# tractor.net
KiCad netlist of a schematic drawn in EAGLE
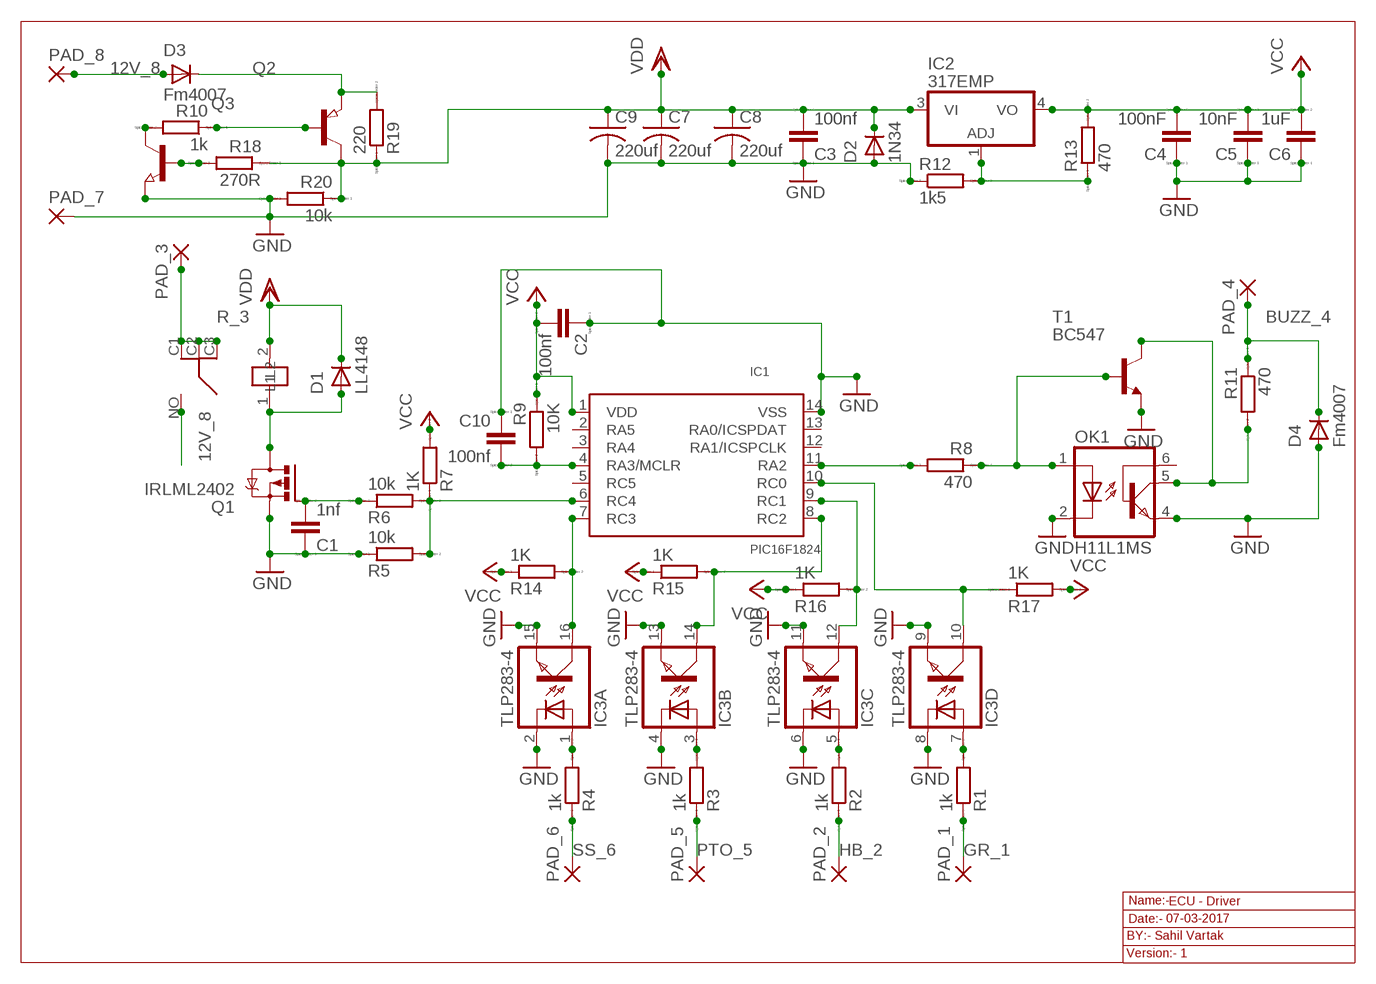
[diagram p0: schematic, sheet 1]

(export (version "E")
  (design (tool "Eeschema 10.0.6"))
  (components
    (comp (ref "C1")
      (value "1nf")
      (footprint "eagle-import:C0603")
      (libsource (lib "eagle-import") (part "CC0603"))
    )
    (comp (ref "C2")
      (value "100nf")
      (footprint "eagle-import:C0603")
      (libsource (lib "eagle-import") (part "CC0603"))
    )
    (comp (ref "C3")
      (value "100nf")
      (footprint "eagle-import:C0603")
      (libsource (lib "eagle-import") (part "CC0603"))
    )
    (comp (ref "C4")
      (value "100nF")
      (footprint "eagle-import:C0603")
      (libsource (lib "eagle-import") (part "CC0603"))
    )
    (comp (ref "C5")
      (value "10nF")
      (footprint "eagle-import:C0603")
      (libsource (lib "eagle-import") (part "CC0603"))
    )
    (comp (ref "C6")
      (value "1uF")
      (footprint "eagle-import:C0603")
      (libsource (lib "eagle-import") (part "CC0603"))
    )
    (comp (ref "C7")
      (value "220uf")
      (footprint "eagle-import:C025-025X050")
      (libsource (lib "eagle-import") (part "C-US025-025X050"))
    )
    (comp (ref "C8")
      (value "220uf")
      (footprint "eagle-import:C025-025X050")
      (libsource (lib "eagle-import") (part "C-US025-025X050"))
    )
    (comp (ref "C9")
      (value "220uf")
      (footprint "eagle-import:C025-025X050")
      (libsource (lib "eagle-import") (part "C-US025-025X050"))
    )
    (comp (ref "C10")
      (value "100nf")
      (footprint "eagle-import:C0603")
      (libsource (lib "eagle-import") (part "CC0603"))
    )
    (comp (ref "D1")
      (value "LL4148")
      (footprint "eagle-import:SMA-DO214AC")
      (libsource (lib "eagle-import") (part "GF1"))
    )
    (comp (ref "D2")
      (value "1N34")
      (footprint "eagle-import:SMA-DO214AC")
      (libsource (lib "eagle-import") (part "GF1"))
    )
    (comp (ref "D3")
      (value "Fm4007")
      (footprint "eagle-import:SMA-DO214AC")
      (libsource (lib "eagle-import") (part "GF1"))
    )
    (comp (ref "D4")
      (value "Fm4007")
      (footprint "eagle-import:SMA-DO214AC")
      (libsource (lib "eagle-import") (part "GF1"))
    )
    (comp (ref "IC1")
      (value "PIC16F1824")
      (footprint "eagle-import:SO-14")
      (libsource (lib "eagle-import") (part "PIC16F1824"))
    )
    (comp (ref "IC2")
      (value "317EMP")
      (footprint "eagle-import:SOT223")
      (libsource (lib "eagle-import") (part "317EMP"))
    )
    (comp (ref "IC3")
      (value "TLP283-4")
      (footprint "eagle-import:MINI-FLAT-16")
      (libsource (lib "eagle-import") (part "TLP283-4"))
    )
    (comp (ref "K2")
      (value "RL703")
      (footprint "eagle-import:RL703")
      (libsource (lib "eagle-import") (part "RL703"))
    )
    (comp (ref "OK1")
      (value "H11L1MS")
      (footprint "eagle-import:DIL6-SMD")
      (libsource (lib "eagle-import") (part "H11LMS1"))
    )
    (comp (ref "PAD_1")
      (value "2,54/1,1")
      (footprint "eagle-import:2,54_1,1")
      (libsource (lib "eagle-import") (part "2,54/1,1"))
    )
    (comp (ref "PAD_2")
      (value "2,54/1,1")
      (footprint "eagle-import:2,54_1,1")
      (libsource (lib "eagle-import") (part "2,54/1,1"))
    )
    (comp (ref "PAD_3")
      (value "2,54/1,1")
      (footprint "eagle-import:2,54_1,1")
      (libsource (lib "eagle-import") (part "2,54/1,1"))
    )
    (comp (ref "PAD_4")
      (value "2,54/1,1")
      (footprint "eagle-import:2,54_1,1")
      (libsource (lib "eagle-import") (part "2,54/1,1"))
    )
    (comp (ref "PAD_5")
      (value "2,54/1,1")
      (footprint "eagle-import:2,54_1,1")
      (libsource (lib "eagle-import") (part "2,54/1,1"))
    )
    (comp (ref "PAD_6")
      (value "2,54/1,1")
      (footprint "eagle-import:2,54_1,1")
      (libsource (lib "eagle-import") (part "2,54/1,1"))
    )
    (comp (ref "PAD_7")
      (value "2,54/1,1")
      (footprint "eagle-import:2,54_1,1")
      (libsource (lib "eagle-import") (part "2,54/1,1"))
    )
    (comp (ref "PAD_8")
      (value "2,54/1,1")
      (footprint "eagle-import:2,54_1,1")
      (libsource (lib "eagle-import") (part "2,54/1,1"))
    )
    (comp (ref "Q1")
      (value "IRLML2402")
      (footprint "eagle-import:MICRO3")
      (libsource (lib "eagle-import") (part "IRLML5203"))
    )
    (comp (ref "Q2")
      (value "PNP-TRANSISTOR_SOT23")
      (footprint "eagle-import:SOT23")
      (libsource (lib "eagle-import") (part "PNP-TRANSISTOR_SOT23"))
    )
    (comp (ref "Q3")
      (value "NPN-TRANSISTOR_SOT23")
      (footprint "eagle-import:SOT23")
      (libsource (lib "eagle-import") (part "NPN-TRANSISTOR_SOT23"))
    )
    (comp (ref "R1")
      (value "1k")
      (footprint "eagle-import:R0603")
      (libsource (lib "eagle-import") (part "RR0603"))
    )
    (comp (ref "R2")
      (value "1k")
      (footprint "eagle-import:R0603")
      (libsource (lib "eagle-import") (part "RR0603"))
    )
    (comp (ref "R3")
      (value "1k")
      (footprint "eagle-import:R0603")
      (libsource (lib "eagle-import") (part "RR0603"))
    )
    (comp (ref "R4")
      (value "1k")
      (footprint "eagle-import:R0603")
      (libsource (lib "eagle-import") (part "RR0603"))
    )
    (comp (ref "R5")
      (value "10k")
      (footprint "eagle-import:R0603")
      (libsource (lib "eagle-import") (part "RR0603"))
    )
    (comp (ref "R6")
      (value "10k")
      (footprint "eagle-import:R0603")
      (libsource (lib "eagle-import") (part "RR0603"))
    )
    (comp (ref "R7")
      (value "1K")
      (footprint "eagle-import:R0603")
      (libsource (lib "eagle-import") (part "RR0603"))
    )
    (comp (ref "R8")
      (value "470")
      (footprint "eagle-import:R0603")
      (libsource (lib "eagle-import") (part "RR0603"))
    )
    (comp (ref "R9")
      (value "10K")
      (footprint "eagle-import:R0603")
      (libsource (lib "eagle-import") (part "RR0603"))
    )
    (comp (ref "R10")
      (value "1k")
      (footprint "eagle-import:R0603")
      (libsource (lib "eagle-import") (part "RR0603"))
    )
    (comp (ref "R11")
      (value "470")
      (footprint "eagle-import:R0603")
      (libsource (lib "eagle-import") (part "RR0603"))
    )
    (comp (ref "R12")
      (value "1k5")
      (footprint "eagle-import:R0603")
      (libsource (lib "eagle-import") (part "RR0603"))
    )
    (comp (ref "R13")
      (value "470")
      (footprint "eagle-import:R0603")
      (libsource (lib "eagle-import") (part "RR0603"))
    )
    (comp (ref "R14")
      (value "1K")
      (footprint "eagle-import:R0603")
      (libsource (lib "eagle-import") (part "RR0603"))
    )
    (comp (ref "R15")
      (value "1K")
      (footprint "eagle-import:R0603")
      (libsource (lib "eagle-import") (part "RR0603"))
    )
    (comp (ref "R16")
      (value "1K")
      (footprint "eagle-import:R0603")
      (libsource (lib "eagle-import") (part "RR0603"))
    )
    (comp (ref "R17")
      (value "1K")
      (footprint "eagle-import:R0603")
      (libsource (lib "eagle-import") (part "RR0603"))
    )
    (comp (ref "R18")
      (value "270R")
      (footprint "eagle-import:R0603")
      (libsource (lib "eagle-import") (part "RR0603"))
    )
    (comp (ref "R19")
      (value "220")
      (footprint "eagle-import:R0603")
      (libsource (lib "eagle-import") (part "RR0603"))
    )
    (comp (ref "R20")
      (value "10k")
      (footprint "eagle-import:R0603")
      (libsource (lib "eagle-import") (part "RR0603"))
    )
    (comp (ref "T1")
      (value "BC547")
      (footprint "eagle-import:TO92")
      (libsource (lib "eagle-import") (part "BC547"))
    )
  )
  (nets
    (net (code "1") (name "/12V_8") (class "Default")
      (node (ref "D3") (pin "A") (pinfunction "A_A") (pintype "passive"))
      (node (ref "K2") (pin "NO") (pinfunction "NO_NO") (pintype "bidirectional"))
      (node (ref "PAD_8") (pin "1") (pinfunction "P_1") (pintype "passive"))
    )
    (net (code "2") (name "/BUZZ_4") (class "Default")
      (node (ref "D4") (pin "K") (pinfunction "C_K") (pintype "passive"))
      (node (ref "PAD_4") (pin "1") (pinfunction "P_1") (pintype "passive"))
      (node (ref "R11") (pin "1") (pinfunction "1_1") (pintype "passive"))
    )
    (net (code "3") (name "/GR_1") (class "Default")
      (node (ref "PAD_1") (pin "1") (pinfunction "P_1") (pintype "passive"))
      (node (ref "R1") (pin "1") (pinfunction "1_1") (pintype "passive"))
    )
    (net (code "4") (name "/HB_2") (class "Default")
      (node (ref "PAD_2") (pin "1") (pinfunction "P_1") (pintype "passive"))
      (node (ref "R2") (pin "1") (pinfunction "1_1") (pintype "passive"))
    )
    (net (code "5") (name "/PTO_5") (class "Default")
      (node (ref "PAD_5") (pin "1") (pinfunction "P_1") (pintype "passive"))
      (node (ref "R3") (pin "1") (pinfunction "1_1") (pintype "passive"))
    )
    (net (code "6") (name "/R_3") (class "Default")
      (node (ref "K2") (pin "C1") (pinfunction "C1_C1") (pintype "bidirectional"))
      (node (ref "K2") (pin "C2") (pinfunction "C2_C2") (pintype "bidirectional"))
      (node (ref "K2") (pin "C3") (pinfunction "C3_C3") (pintype "bidirectional"))
      (node (ref "PAD_3") (pin "1") (pinfunction "P_1") (pintype "passive"))
    )
    (net (code "7") (name "/SS_6") (class "Default")
      (node (ref "PAD_6") (pin "1") (pinfunction "P_1") (pintype "passive"))
      (node (ref "R4") (pin "1") (pinfunction "1_1") (pintype "passive"))
    )
    (net (code "8") (name "GND") (class "Default")
      (node (ref "C1") (pin "1") (pinfunction "1_1") (pintype "passive"))
      (node (ref "C10") (pin "1") (pinfunction "1_1") (pintype "passive"))
      (node (ref "C2") (pin "1") (pinfunction "1_1") (pintype "passive"))
      (node (ref "C3") (pin "1") (pinfunction "1_1") (pintype "passive"))
      (node (ref "C4") (pin "1") (pinfunction "1_1") (pintype "passive"))
      (node (ref "C5") (pin "1") (pinfunction "1_1") (pintype "passive"))
      (node (ref "C6") (pin "1") (pinfunction "1_1") (pintype "passive"))
      (node (ref "C7") (pin "2") (pinfunction "2_2") (pintype "passive"))
      (node (ref "C8") (pin "2") (pinfunction "2_2") (pintype "passive"))
      (node (ref "C9") (pin "2") (pinfunction "2_2") (pintype "passive"))
      (node (ref "D2") (pin "A") (pinfunction "A_A") (pintype "passive"))
      (node (ref "D4") (pin "A") (pinfunction "A_A") (pintype "passive"))
      (node (ref "IC1") (pin "14") (pinfunction "VSS_14") (pintype "bidirectional"))
      (node (ref "IC3") (pin "11") (pinfunction "EMIT_11") (pintype "passive"))
      (node (ref "IC3") (pin "13") (pinfunction "EMIT_13") (pintype "passive"))
      (node (ref "IC3") (pin "15") (pinfunction "EMIT_15") (pintype "passive"))
      (node (ref "IC3") (pin "2") (pinfunction "C_2") (pintype "passive"))
      (node (ref "IC3") (pin "4") (pinfunction "C_4") (pintype "passive"))
      (node (ref "IC3") (pin "6") (pinfunction "C_6") (pintype "passive"))
      (node (ref "IC3") (pin "8") (pinfunction "C_8") (pintype "passive"))
      (node (ref "IC3") (pin "9") (pinfunction "EMIT_9") (pintype "passive"))
      (node (ref "OK1") (pin "2") (pinfunction "C_2") (pintype "passive"))
      (node (ref "OK1") (pin "4") (pinfunction "EMI_4") (pintype "passive"))
      (node (ref "PAD_7") (pin "1") (pinfunction "P_1") (pintype "passive"))
      (node (ref "Q1") (pin "2") (pinfunction "S_2") (pintype "passive"))
      (node (ref "Q3") (pin "2") (pinfunction "E_2") (pintype "passive"))
      (node (ref "R12") (pin "1") (pinfunction "1_1") (pintype "passive"))
      (node (ref "R20") (pin "2") (pinfunction "2_2") (pintype "passive"))
      (node (ref "R5") (pin "1") (pinfunction "1_1") (pintype "passive"))
      (node (ref "T1") (pin "1") (pinfunction "E_1") (pintype "passive"))
    )
    (net (code "9") (name "Net-(D3-C)") (class "Default")
      (node (ref "D3") (pin "K") (pinfunction "C_K") (pintype "passive"))
      (node (ref "Q2") (pin "2") (pinfunction "E_2") (pintype "passive"))
      (node (ref "R19") (pin "2") (pinfunction "2_2") (pintype "passive"))
    )
    (net (code "10") (name "Net-(IC1-RA2)") (class "Default")
      (node (ref "IC1") (pin "11") (pinfunction "RA2_11") (pintype "bidirectional"))
      (node (ref "R8") (pin "2") (pinfunction "2_2") (pintype "passive"))
    )
    (net (code "11") (name "Net-(IC1-RA3{slash}MCLR)") (class "Default")
      (node (ref "C10") (pin "2") (pinfunction "2_2") (pintype "passive"))
      (node (ref "IC1") (pin "4") (pinfunction "RA3/MCLR_4") (pintype "bidirectional"))
      (node (ref "R9") (pin "2") (pinfunction "2_2") (pintype "passive"))
    )
    (net (code "12") (name "Net-(IC1-RC0)") (class "Default")
      (node (ref "IC1") (pin "10") (pinfunction "RC0_10") (pintype "bidirectional"))
      (node (ref "IC3") (pin "10") (pinfunction "COL_10") (pintype "passive"))
      (node (ref "R17") (pin "1") (pinfunction "1_1") (pintype "passive"))
    )
    (net (code "13") (name "Net-(IC1-RC1)") (class "Default")
      (node (ref "IC1") (pin "9") (pinfunction "RC1_9") (pintype "bidirectional"))
      (node (ref "IC3") (pin "12") (pinfunction "COL_12") (pintype "passive"))
      (node (ref "R16") (pin "2") (pinfunction "2_2") (pintype "passive"))
    )
    (net (code "14") (name "Net-(IC1-RC2)") (class "Default")
      (node (ref "IC1") (pin "8") (pinfunction "RC2_8") (pintype "bidirectional"))
      (node (ref "IC3") (pin "14") (pinfunction "COL_14") (pintype "passive"))
      (node (ref "R15") (pin "2") (pinfunction "2_2") (pintype "passive"))
    )
    (net (code "15") (name "Net-(IC1-RC3)") (class "Default")
      (node (ref "IC1") (pin "7") (pinfunction "RC3_7") (pintype "bidirectional"))
      (node (ref "IC3") (pin "16") (pinfunction "COL_16") (pintype "passive"))
      (node (ref "R14") (pin "2") (pinfunction "2_2") (pintype "passive"))
    )
    (net (code "16") (name "Net-(IC1-RC4)") (class "Default")
      (node (ref "IC1") (pin "6") (pinfunction "RC4_6") (pintype "bidirectional"))
      (node (ref "R5") (pin "2") (pinfunction "2_2") (pintype "passive"))
      (node (ref "R6") (pin "2") (pinfunction "2_2") (pintype "passive"))
      (node (ref "R7") (pin "1") (pinfunction "1_1") (pintype "passive"))
    )
    (net (code "17") (name "Net-(IC2-ADJ)") (class "Default")
      (node (ref "IC2") (pin "1") (pinfunction "ADJ_1") (pintype "input"))
      (node (ref "R12") (pin "2") (pinfunction "2_2") (pintype "passive"))
      (node (ref "R13") (pin "1") (pinfunction "1_1") (pintype "passive"))
    )
    (net (code "18") (name "Net-(IC3A-A)") (class "Default")
      (node (ref "IC3") (pin "1") (pinfunction "A_1") (pintype "passive"))
      (node (ref "R4") (pin "2") (pinfunction "2_2") (pintype "passive"))
    )
    (net (code "19") (name "Net-(IC3B-A)") (class "Default")
      (node (ref "IC3") (pin "3") (pinfunction "A_3") (pintype "passive"))
      (node (ref "R3") (pin "2") (pinfunction "2_2") (pintype "passive"))
    )
    (net (code "20") (name "Net-(IC3C-A)") (class "Default")
      (node (ref "IC3") (pin "5") (pinfunction "A_5") (pintype "passive"))
      (node (ref "R2") (pin "2") (pinfunction "2_2") (pintype "passive"))
    )
    (net (code "21") (name "Net-(IC3D-A)") (class "Default")
      (node (ref "IC3") (pin "7") (pinfunction "A_7") (pintype "passive"))
      (node (ref "R1") (pin "2") (pinfunction "2_2") (pintype "passive"))
    )
    (net (code "22") (name "Net-(K2-L2)") (class "Default")
      (node (ref "D1") (pin "A") (pinfunction "A_A") (pintype "passive"))
      (node (ref "K2") (pin "1") (pinfunction "L2_1") (pintype "bidirectional"))
      (node (ref "Q1") (pin "3") (pinfunction "D_3") (pintype "passive"))
    )
    (net (code "23") (name "Net-(OK1-A)") (class "Default")
      (node (ref "OK1") (pin "1") (pinfunction "A_1") (pintype "passive"))
      (node (ref "R8") (pin "1") (pinfunction "1_1") (pintype "passive"))
      (node (ref "T1") (pin "2") (pinfunction "B_2") (pintype "passive"))
    )
    (net (code "24") (name "Net-(OK1-COL)") (class "Default")
      (node (ref "OK1") (pin "5") (pinfunction "COL_5") (pintype "passive"))
      (node (ref "R11") (pin "2") (pinfunction "2_2") (pintype "passive"))
      (node (ref "T1") (pin "3") (pinfunction "C_3") (pintype "passive"))
    )
    (net (code "25") (name "Net-(Q1-G)") (class "Default")
      (node (ref "C1") (pin "2") (pinfunction "2_2") (pintype "passive"))
      (node (ref "Q1") (pin "1") (pinfunction "G_1") (pintype "passive"))
      (node (ref "R6") (pin "1") (pinfunction "1_1") (pintype "passive"))
    )
    (net (code "26") (name "Net-(Q2-B)") (class "Default")
      (node (ref "Q2") (pin "1") (pinfunction "B_1") (pintype "passive"))
      (node (ref "R10") (pin "1") (pinfunction "1_1") (pintype "passive"))
    )
    (net (code "27") (name "Net-(Q3-B)") (class "Default")
      (node (ref "Q3") (pin "1") (pinfunction "B_1") (pintype "passive"))
      (node (ref "R18") (pin "2") (pinfunction "2_2") (pintype "passive"))
    )
    (net (code "28") (name "Net-(Q3-C)") (class "Default")
      (node (ref "Q3") (pin "3") (pinfunction "C_3") (pintype "passive"))
      (node (ref "R10") (pin "2") (pinfunction "2_2") (pintype "passive"))
    )
    (net (code "29") (name "VCC") (class "Default")
      (node (ref "C2") (pin "2") (pinfunction "2_2") (pintype "passive"))
      (node (ref "C4") (pin "2") (pinfunction "2_2") (pintype "passive"))
      (node (ref "C5") (pin "2") (pinfunction "2_2") (pintype "passive"))
      (node (ref "C6") (pin "2") (pinfunction "2_2") (pintype "passive"))
      (node (ref "IC1") (pin "1") (pinfunction "VDD_1") (pintype "bidirectional"))
      (node (ref "IC2") (pin "4") (pinfunction "VO_4") (pintype "passive"))
      (node (ref "R13") (pin "2") (pinfunction "2_2") (pintype "passive"))
      (node (ref "R14") (pin "1") (pinfunction "1_1") (pintype "passive"))
      (node (ref "R15") (pin "1") (pinfunction "1_1") (pintype "passive"))
      (node (ref "R16") (pin "1") (pinfunction "1_1") (pintype "passive"))
      (node (ref "R17") (pin "2") (pinfunction "2_2") (pintype "passive"))
      (node (ref "R7") (pin "2") (pinfunction "2_2") (pintype "passive"))
      (node (ref "R9") (pin "1") (pinfunction "1_1") (pintype "passive"))
    )
    (net (code "30") (name "VDD") (class "Default")
      (node (ref "C3") (pin "2") (pinfunction "2_2") (pintype "passive"))
      (node (ref "C7") (pin "1") (pinfunction "1_1") (pintype "passive"))
      (node (ref "C8") (pin "1") (pinfunction "1_1") (pintype "passive"))
      (node (ref "C9") (pin "1") (pinfunction "1_1") (pintype "passive"))
      (node (ref "D1") (pin "K") (pinfunction "C_K") (pintype "passive"))
      (node (ref "D2") (pin "K") (pinfunction "C_K") (pintype "passive"))
      (node (ref "IC2") (pin "3") (pinfunction "VI_3") (pintype "input"))
      (node (ref "K2") (pin "2") (pinfunction "L1_2") (pintype "bidirectional"))
      (node (ref "Q2") (pin "3") (pinfunction "C_3") (pintype "passive"))
      (node (ref "R18") (pin "1") (pinfunction "1_1") (pintype "passive"))
      (node (ref "R19") (pin "1") (pinfunction "1_1") (pintype "passive"))
      (node (ref "R20") (pin "1") (pinfunction "1_1") (pintype "passive"))
    )
    (net (code "31") (name "unconnected-(IC1-RA0{slash}ICSPDAT-Pad13)") (class "Default")
      (node (ref "IC1") (pin "13") (pinfunction "RA0/ICSPDAT_13") (pintype "bidirectional"))
    )
    (net (code "32") (name "unconnected-(IC1-RA1{slash}ICSPCLK-Pad12)") (class "Default")
      (node (ref "IC1") (pin "12") (pinfunction "RA1/ICSPCLK_12") (pintype "bidirectional"))
    )
    (net (code "33") (name "unconnected-(IC1-RA4-Pad3)") (class "Default")
      (node (ref "IC1") (pin "3") (pinfunction "RA4_3") (pintype "bidirectional"))
    )
    (net (code "34") (name "unconnected-(IC1-RA5-Pad2)") (class "Default")
      (node (ref "IC1") (pin "2") (pinfunction "RA5_2") (pintype "bidirectional"))
    )
    (net (code "35") (name "unconnected-(IC1-RC5-Pad5)") (class "Default")
      (node (ref "IC1") (pin "5") (pinfunction "RC5_5") (pintype "bidirectional"))
    )
    (net (code "36") (name "unconnected-(OK1-BAS-Pad6)") (class "Default")
      (node (ref "OK1") (pin "6") (pinfunction "BAS_6") (pintype "passive"))
    )
  )
)
